# GSM.net
KiCad netlist of a schematic drawn in Altium Designer
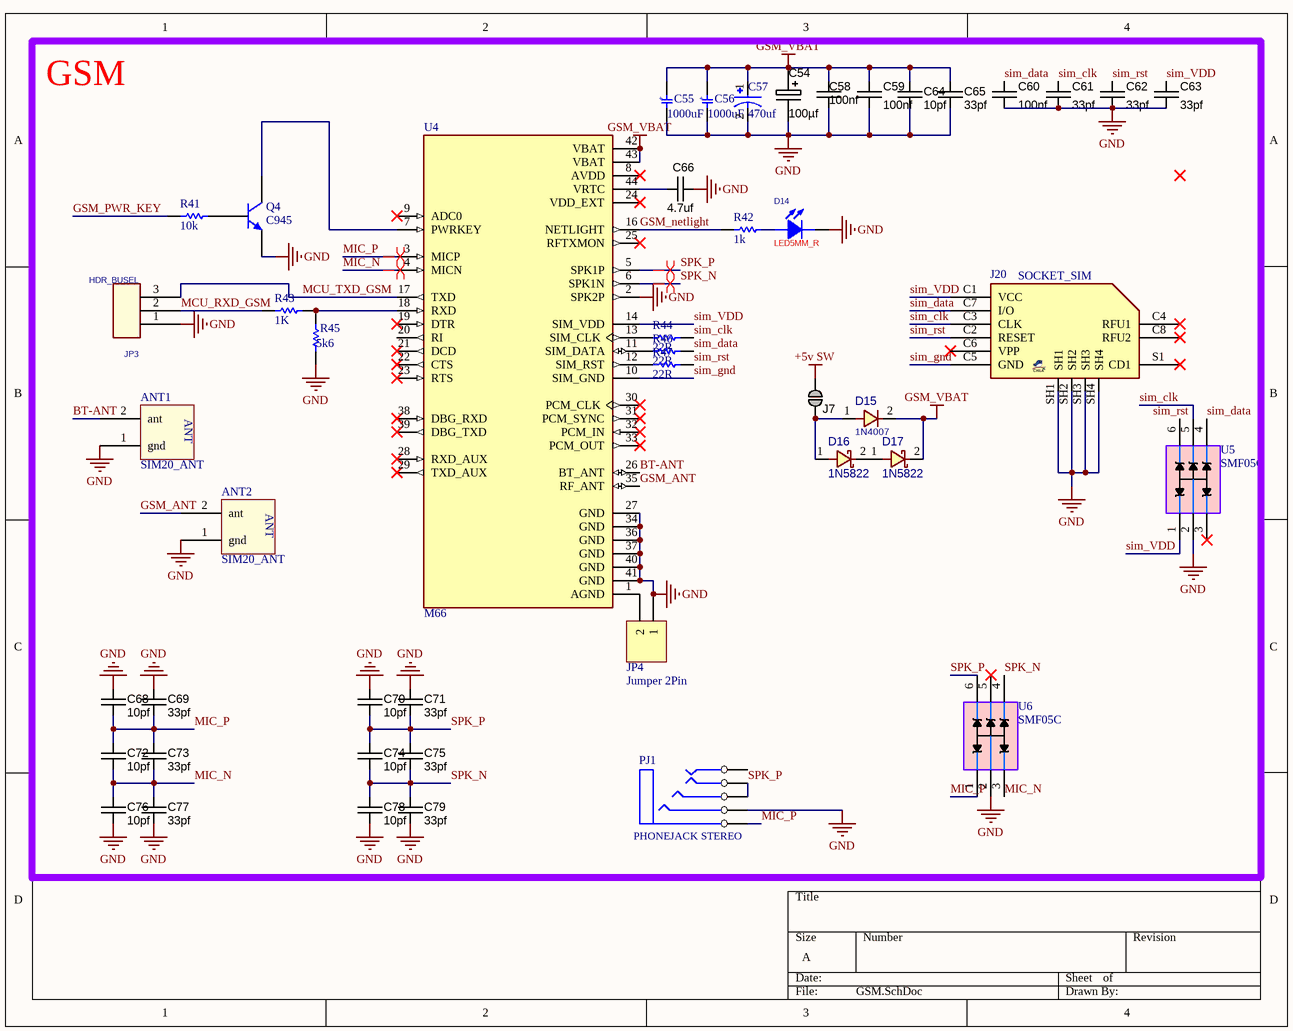
[diagram p0: GSM.SchDoc]

(export (version "E")
  (design (tool "Eeschema 10.0.6"))
  (components
    (comp (ref "ANT1")
      (value "SIM20_ANT")
      (footprint "MY_SIM20_ANT")
      (description "ANT")
      (libsource (lib "altium-import") (part "root_2_SIM20_ANT_"))
    )
    (comp (ref "ANT2")
      (value "SIM20_ANT")
      (footprint "MY_SIM20_ANT")
      (description "ANT")
      (libsource (lib "altium-import") (part "root_2_SIM20_ANT_"))
    )
    (comp (ref "C54")
      (value "100µf")
      (footprint "CAPMP3528X210N")
      (description "Capacitor SMD Tantalum 100uF 20% 6.3V 1210")
      (fields (field (name "TOLERANCE") "±20%") (field (name "Comment") "100uf"))
      (libsource (lib "altium-import") (part "root_0_CAPT_100u_1210_6V3_"))
    )
    (comp (ref "C55")
      (value "1000uF")
      (footprint "Elko G")
      (description "Capacitor Electrical SMD")
      (libsource (lib "Capacitor") (part "Capacitor Electrical SMD"))
    )
    (comp (ref "C56")
      (value "1000uF")
      (footprint "Elko G")
      (description "Capacitor Electrical SMD")
      (libsource (lib "Capacitor") (part "Capacitor Electrical SMD"))
    )
    (comp (ref "C57")
      (value "470uf")
      (footprint "CAP_4TPB330ML")
      (fields (field (name "MP") "4TPB330ML") (field (name "MF") "Sanyo Electric"))
      (libsource (lib "4TPB330ML") (part "4TPB330ML"))
    )
    (comp (ref "C58")
      (value "100nf")
      (footprint "CAPC1608X90N")
      (description "Capacitor SMD Cer 100nF 10% 50V X7R 0603")
      (fields (field (name "TOLERANCE") "±10%"))
      (libsource (lib "altium-import") (part "root_2_CAPC_100n_0603_X7R_50V_10%_"))
    )
    (comp (ref "C59")
      (value "100nf")
      (footprint "CAPC1608X90N")
      (description "Capacitor SMD Cer 100nF 10% 50V X7R 0603")
      (fields (field (name "TOLERANCE") "±10%"))
      (libsource (lib "altium-import") (part "root_2_CAPC_100n_0603_X7R_50V_10%_"))
    )
    (comp (ref "C60")
      (value "100nf")
      (footprint "CAPC1608X90N")
      (description "Capacitor SMD Cer 100nF 10% 50V X7R 0603")
      (fields (field (name "TOLERANCE") "±10%"))
      (libsource (lib "altium-import") (part "root_2_CAPC_100n_0603_X7R_50V_10%_"))
    )
    (comp (ref "C61")
      (value "33pf")
      (footprint "CAPC1608X90N")
      (description "Capacitor SMD Cer 100nF 10% 50V X7R 0603")
      (fields (field (name "TOLERANCE") "±10%"))
      (libsource (lib "altium-import") (part "root_2_CAPC_100n_0603_X7R_50V_10%_"))
    )
    (comp (ref "C62")
      (value "33pf")
      (footprint "CAPC1608X90N")
      (description "Capacitor SMD Cer 100nF 10% 50V X7R 0603")
      (fields (field (name "TOLERANCE") "±10%"))
      (libsource (lib "altium-import") (part "root_2_CAPC_100n_0603_X7R_50V_10%_"))
    )
    (comp (ref "C63")
      (value "33pf")
      (footprint "CAPC1608X90N")
      (description "Capacitor SMD Cer 100nF 10% 50V X7R 0603")
      (fields (field (name "TOLERANCE") "±10%"))
      (libsource (lib "altium-import") (part "root_2_CAPC_100n_0603_X7R_50V_10%_"))
    )
    (comp (ref "C64")
      (value "10pf")
      (footprint "CAPC1608X90N")
      (description "Capacitor SMD Cer 100nF 10% 50V X7R 0603")
      (fields (field (name "TOLERANCE") "±10%"))
      (libsource (lib "altium-import") (part "root_2_CAPC_100n_0603_X7R_50V_10%_"))
    )
    (comp (ref "C65")
      (value "33pf")
      (footprint "CAPC1608X90N")
      (description "Capacitor SMD Cer 100nF 10% 50V X7R 0603")
      (fields (field (name "TOLERANCE") "±10%"))
      (libsource (lib "altium-import") (part "root_2_CAPC_100n_0603_X7R_50V_10%_"))
    )
    (comp (ref "C66")
      (value "4.7uf")
      (footprint "CAPC1608X90N")
      (description "Capacitor SMD Cer 100nF 10% 50V X7R 0603")
      (fields (field (name "TOLERANCE") "±10%"))
      (libsource (lib "altium-import") (part "root_1_CAPC_100n_0603_X7R_50V_10%_"))
    )
    (comp (ref "C68")
      (value "10pf")
      (footprint "CAPC1608X90N")
      (description "Capacitor SMD Cer 100nF 10% 50V X7R 0603")
      (fields (field (name "TOLERANCE") "±10%"))
      (libsource (lib "altium-import") (part "root_2_CAPC_100n_0603_X7R_50V_10%_"))
    )
    (comp (ref "C69")
      (value "33pf")
      (footprint "CAPC1608X90N")
      (description "Capacitor SMD Cer 100nF 10% 50V X7R 0603")
      (fields (field (name "TOLERANCE") "±10%"))
      (libsource (lib "altium-import") (part "root_2_CAPC_100n_0603_X7R_50V_10%_"))
    )
    (comp (ref "C70")
      (value "10pf")
      (footprint "CAPC1608X90N")
      (description "Capacitor SMD Cer 100nF 10% 50V X7R 0603")
      (fields (field (name "TOLERANCE") "±10%"))
      (libsource (lib "altium-import") (part "root_2_CAPC_100n_0603_X7R_50V_10%_"))
    )
    (comp (ref "C71")
      (value "33pf")
      (footprint "CAPC1608X90N")
      (description "Capacitor SMD Cer 100nF 10% 50V X7R 0603")
      (fields (field (name "TOLERANCE") "±10%"))
      (libsource (lib "altium-import") (part "root_2_CAPC_100n_0603_X7R_50V_10%_"))
    )
    (comp (ref "C72")
      (value "10pf")
      (footprint "CAPC1608X90N")
      (description "Capacitor SMD Cer 100nF 10% 50V X7R 0603")
      (fields (field (name "TOLERANCE") "±10%"))
      (libsource (lib "altium-import") (part "root_2_CAPC_100n_0603_X7R_50V_10%_"))
    )
    (comp (ref "C73")
      (value "33pf")
      (footprint "CAPC1608X90N")
      (description "Capacitor SMD Cer 100nF 10% 50V X7R 0603")
      (fields (field (name "TOLERANCE") "±10%"))
      (libsource (lib "altium-import") (part "root_2_CAPC_100n_0603_X7R_50V_10%_"))
    )
    (comp (ref "C74")
      (value "10pf")
      (footprint "CAPC1608X90N")
      (description "Capacitor SMD Cer 100nF 10% 50V X7R 0603")
      (fields (field (name "TOLERANCE") "±10%"))
      (libsource (lib "altium-import") (part "root_2_CAPC_100n_0603_X7R_50V_10%_"))
    )
    (comp (ref "C75")
      (value "33pf")
      (footprint "CAPC1608X90N")
      (description "Capacitor SMD Cer 100nF 10% 50V X7R 0603")
      (fields (field (name "TOLERANCE") "±10%"))
      (libsource (lib "altium-import") (part "root_2_CAPC_100n_0603_X7R_50V_10%_"))
    )
    (comp (ref "C76")
      (value "10pf")
      (footprint "CAPC1608X90N")
      (description "Capacitor SMD Cer 100nF 10% 50V X7R 0603")
      (fields (field (name "TOLERANCE") "±10%"))
      (libsource (lib "altium-import") (part "root_2_CAPC_100n_0603_X7R_50V_10%_"))
    )
    (comp (ref "C77")
      (value "33pf")
      (footprint "CAPC1608X90N")
      (description "Capacitor SMD Cer 100nF 10% 50V X7R 0603")
      (fields (field (name "TOLERANCE") "±10%"))
      (libsource (lib "altium-import") (part "root_2_CAPC_100n_0603_X7R_50V_10%_"))
    )
    (comp (ref "C78")
      (value "10pf")
      (footprint "CAPC1608X90N")
      (description "Capacitor SMD Cer 100nF 10% 50V X7R 0603")
      (fields (field (name "TOLERANCE") "±10%"))
      (libsource (lib "altium-import") (part "root_2_CAPC_100n_0603_X7R_50V_10%_"))
    )
    (comp (ref "C79")
      (value "33pf")
      (footprint "CAPC1608X90N")
      (description "Capacitor SMD Cer 100nF 10% 50V X7R 0603")
      (fields (field (name "TOLERANCE") "±10%"))
      (libsource (lib "altium-import") (part "root_2_CAPC_100n_0603_X7R_50V_10%_"))
    )
    (comp (ref "D14")
      (value "LED5MM_R")
      (footprint "LED5MM_RED")
      (description "LED LIGHTING")
      (fields (field (name "DESIGNER") "Abbas Basereh"))
      (libsource (lib "altium-import") (part "root_0_LED5MM_"))
    )
    (comp (ref "D15")
      (value "1N4007")
      (footprint "D_SMA")
      (description "DIODE, GENERAL PURPOSE, 1000V/1A")
      (fields (field (name "MANF") "Kingtronics") (field (name "MANF_P#") "M7"))
      (libsource (lib "altium-import") (part "root_0_DIODE_SMD_1N4007_"))
    )
    (comp (ref "D16")
      (value "1N5822")
      (footprint "D_SMA")
      (description "DIODE, SCHOTTKY, 40V, 3A")
      (fields (field (name "MANF") "DIODES"))
      (libsource (lib "altium-import") (part "root_0_DIODE_SMD_SCHOTTKY_1N5822_"))
    )
    (comp (ref "D17")
      (value "1N5822")
      (footprint "D_SMA")
      (description "DIODE, SCHOTTKY, 40V, 3A")
      (fields (field (name "MANF") "DIODES"))
      (libsource (lib "altium-import") (part "root_0_DIODE_SMD_SCHOTTKY_1N5822_"))
    )
    (comp (ref "J7")
      (value "Jumper")
      (footprint "JUMP1")
      (description "SMD jumper")
      (libsource (lib "Utiliti_Library") (part "JUMP1"))
    )
    (comp (ref "J20")
      (value "SOCKET_SIM")
      (footprint "SIM_MICRO_GCT")
      (description "SOCKET, SIM MICRO, PUSH/PUSH, SIM7100")
      (fields (field (name "MANF") "GCT") (field (name "MANF_P#") "SIM7100"))
      (libsource (lib "socket_card") (part "SIM_MICRO_GCT"))
    )
    (comp (ref "JP3")
      (value "HDR_BUSEL")
      (footprint "HDR_1x3")
      (description "header or jumper box")
      (libsource (lib "2017AbbasBasereh9365731239 -ver1") (part "Header 1x3"))
    )
    (comp (ref "JP4")
      (value "Jumper 2Pin")
      (footprint "Jumper Small - 2.54 - Blue")
      (description "Jumper, 2-Pin")
      (fields (field (name "DESIGNER") "Abbas Basereh"))
      (libsource (lib "altium-import") (part "root_3_Jumper 2Pin_"))
    )
    (comp (ref "PJ1")
      (value "PHONEJACK STEREO")
      (footprint "PHONE-J2-3.5MM")
      (libsource (lib "*") (part "PHONEJACK STEREO SW"))
    )
    (comp (ref "Q4")
      (value "C945")
      (footprint "SOT23_N")
      (description "NPN Silicon Epitaxial Planar Transistor")
      (fields (field (name "PUBLISHER") "Abbas Basereh"))
      (libsource (lib "altium-import") (part "root_0_C945_"))
    )
    (comp (ref "R41")
      (value "10k")
      (footprint "Resistor_SMD_0603 (1608)")
      (description "Resistor 0603")
      (fields (field (name "PUBLISHER") "Seyed Razi Vesali") (field (name "EMAIL") "razi.vesali@gmail.com"))
      (libsource (lib "resistors") (part "Resistor"))
    )
    (comp (ref "R42")
      (value "1k")
      (footprint "Resistor_SMD_0603 (1608)")
      (description "Resistor 0603")
      (fields (field (name "PUBLISHER") "Seyed Razi Vesali") (field (name "EMAIL") "razi.vesali@gmail.com"))
      (libsource (lib "resistors") (part "Resistor"))
    )
    (comp (ref "R43")
      (value "1K")
      (footprint "Resistor_SMD_0603 (1608)")
      (description "Resistor 0603")
      (fields (field (name "PUBLISHER") "Seyed Razi Vesali") (field (name "EMAIL") "razi.vesali@gmail.com"))
      (libsource (lib "resistors") (part "Resistor"))
    )
    (comp (ref "R44")
      (value "22R")
      (footprint "Resistor_SMD_0603 (1608)")
      (description "Resistor 0603")
      (fields (field (name "PUBLISHER") "Seyed Razi Vesali") (field (name "EMAIL") "razi.vesali@gmail.com"))
      (libsource (lib "resistors") (part "Resistor"))
    )
    (comp (ref "R45")
      (value "5k6")
      (footprint "Resistor_SMD_0603 (1608)")
      (description "Resistor 0603")
      (fields (field (name "PUBLISHER") "Seyed Razi Vesali") (field (name "EMAIL") "razi.vesali@gmail.com"))
      (libsource (lib "resistors") (part "Resistor"))
    )
    (comp (ref "R46")
      (value "22R")
      (footprint "Resistor_SMD_0603 (1608)")
      (description "Resistor 0603")
      (fields (field (name "PUBLISHER") "Seyed Razi Vesali") (field (name "EMAIL") "razi.vesali@gmail.com"))
      (libsource (lib "resistors") (part "Resistor"))
    )
    (comp (ref "R47")
      (value "22R")
      (footprint "Resistor_SMD_0603 (1608)")
      (description "Resistor 0603")
      (fields (field (name "PUBLISHER") "Seyed Razi Vesali") (field (name "EMAIL") "razi.vesali@gmail.com"))
      (libsource (lib "resistors") (part "Resistor"))
    )
    (comp (ref "U4")
      (value "M66")
      (footprint "XCVR_M66")
      (fields (field (name "MF") "Quectel"))
      (libsource (lib "altium-import") (part "root_0_M66_"))
    )
    (comp (ref "U5")
      (value "SMF05C")
      (footprint "SC706")
      (description "TVS Diode Array  For ESD and Latch-Up Protection")
      (libsource (lib "altium-import") (part "root_1_TVS Diode_"))
    )
    (comp (ref "U6")
      (value "SMF05C")
      (footprint "SC706")
      (description "TVS Diode Array  For ESD and Latch-Up Protection")
      (libsource (lib "altium-import") (part "root_1_TVS Diode_"))
    )
  )
  (nets
    (net (code "1") (name "+5v SW") (class "Default") (node (ref "J7") (pin "1") (pintype "passive")))
    (net (code "2") (name "/BT-ANT") (class "Default")
      (node (ref "ANT1") (pin "2") (pinfunction "ant_2") (pintype "passive"))
      (node (ref "U4") (pin "26") (pinfunction "BT_ANT_26") (pintype "bidirectional"))
    )
    (net (code "3") (name "/GSM_ANT") (class "Default")
      (node (ref "ANT2") (pin "2") (pinfunction "ant_2") (pintype "passive"))
      (node (ref "U4") (pin "35") (pinfunction "RF_ANT_35") (pintype "bidirectional"))
    )
    (net (code "4") (name "/GSM_PWR_KEY") (class "Default")
      (node (ref "R41") (pin "1") (pinfunction "1_1") (pintype "passive"))
    )
    (net (code "5") (name "/GSM_netlight") (class "Default")
      (node (ref "R42") (pin "1") (pinfunction "1_1") (pintype "passive"))
      (node (ref "U4") (pin "16") (pinfunction "NETLIGHT_16") (pintype "output"))
    )
    (net (code "6") (name "/MCU_RXD_GSM") (class "Default")
      (node (ref "JP3") (pin "2") (pinfunction "2_2") (pintype "passive"))
      (node (ref "R43") (pin "1") (pinfunction "1_1") (pintype "passive"))
    )
    (net (code "7") (name "/MCU_TXD_GSM") (class "Default")
      (node (ref "JP3") (pin "3") (pinfunction "3_3") (pintype "passive"))
      (node (ref "U4") (pin "17") (pinfunction "TXD_17") (pintype "output"))
    )
    (net (code "8") (name "/MIC_N") (class "Default")
      (node (ref "C72") (pin "1") (pintype "passive"))
      (node (ref "C73") (pin "1") (pintype "passive"))
      (node (ref "C76") (pin "2") (pintype "passive"))
      (node (ref "C77") (pin "2") (pintype "passive"))
      (node (ref "U4") (pin "4") (pinfunction "MICN_4") (pintype "input"))
      (node (ref "U6") (pin "3") (pinfunction "L3_3") (pintype "passive"))
    )
    (net (code "9") (name "/MIC_P") (class "Default")
      (node (ref "C68") (pin "1") (pintype "passive"))
      (node (ref "C69") (pin "1") (pintype "passive"))
      (node (ref "C72") (pin "2") (pintype "passive"))
      (node (ref "C73") (pin "2") (pintype "passive"))
      (node (ref "PJ1") (pin "MIC") (pinfunction "6_MIC") (pintype "passive"))
      (node (ref "U4") (pin "3") (pinfunction "MICP_3") (pintype "input"))
      (node (ref "U6") (pin "1") (pinfunction "L1_1") (pintype "passive"))
    )
    (net (code "10") (name "/SPK_N") (class "Default")
      (node (ref "C74") (pin "1") (pintype "passive"))
      (node (ref "C75") (pin "1") (pintype "passive"))
      (node (ref "C78") (pin "2") (pintype "passive"))
      (node (ref "C79") (pin "2") (pintype "passive"))
      (node (ref "U4") (pin "6") (pinfunction "SPK1N_6") (pintype "output"))
      (node (ref "U6") (pin "4") (pinfunction "L4_4") (pintype "passive"))
    )
    (net (code "11") (name "/SPK_P") (class "Default")
      (node (ref "C70") (pin "1") (pintype "passive"))
      (node (ref "C71") (pin "1") (pintype "passive"))
      (node (ref "C74") (pin "2") (pintype "passive"))
      (node (ref "C75") (pin "2") (pintype "passive"))
      (node (ref "PJ1") (pin "EL") (pinfunction "3_EL") (pintype "passive"))
      (node (ref "PJ1") (pin "ER") (pinfunction "4_ER") (pintype "passive"))
      (node (ref "U4") (pin "5") (pinfunction "SPK1P_5") (pintype "output"))
      (node (ref "U6") (pin "6") (pinfunction "L6_6") (pintype "passive"))
    )
    (net (code "12") (name "/sim_VDD") (class "Default")
      (node (ref "C63") (pin "2") (pintype "passive"))
      (node (ref "J20") (pin "C1") (pinfunction "VCC_C1") (pintype "passive"))
      (node (ref "U4") (pin "14") (pinfunction "SIM_VDD_14") (pintype "power_in"))
      (node (ref "U5") (pin "1") (pinfunction "L1_1") (pintype "passive"))
    )
    (net (code "13") (name "/sim_clk") (class "Default")
      (node (ref "C61") (pin "2") (pintype "passive"))
      (node (ref "J20") (pin "C3") (pinfunction "CLK_C3") (pintype "passive"))
      (node (ref "R44") (pin "2") (pinfunction "2_2") (pintype "passive"))
      (node (ref "U5") (pin "5") (pinfunction "L5_5") (pintype "passive"))
    )
    (net (code "14") (name "/sim_data") (class "Default")
      (node (ref "C60") (pin "2") (pintype "passive"))
      (node (ref "J20") (pin "C7") (pinfunction "I/O_C7") (pintype "passive"))
      (node (ref "R46") (pin "2") (pinfunction "2_2") (pintype "passive"))
      (node (ref "U5") (pin "4") (pinfunction "L4_4") (pintype "passive"))
    )
    (net (code "15") (name "/sim_gnd") (class "Default")
      (node (ref "J20") (pin "C5") (pinfunction "GND_C5") (pintype "passive"))
      (node (ref "U4") (pin "10") (pinfunction "SIM_GND_10") (pintype "power_in"))
    )
    (net (code "16") (name "/sim_rst") (class "Default")
      (node (ref "C62") (pin "2") (pintype "passive"))
      (node (ref "J20") (pin "C2") (pinfunction "RESET_C2") (pintype "passive"))
      (node (ref "R47") (pin "2") (pinfunction "2_2") (pintype "passive"))
    )
    (net (code "17") (name "GND") (class "Default")
      (node (ref "ANT1") (pin "1") (pinfunction "gnd_1") (pintype "passive"))
      (node (ref "ANT2") (pin "1") (pinfunction "gnd_1") (pintype "passive"))
      (node (ref "C54") (pin "2") (pintype "passive"))
      (node (ref "C55") (pin "1") (pinfunction "1_1") (pintype "passive"))
      (node (ref "C56") (pin "1") (pinfunction "1_1") (pintype "passive"))
      (node (ref "C57") (pin "2") (pinfunction "2_2") (pintype "passive"))
      (node (ref "C58") (pin "1") (pintype "passive"))
      (node (ref "C59") (pin "1") (pintype "passive"))
      (node (ref "C60") (pin "1") (pintype "passive"))
      (node (ref "C61") (pin "1") (pintype "passive"))
      (node (ref "C62") (pin "1") (pintype "passive"))
      (node (ref "C63") (pin "1") (pintype "passive"))
      (node (ref "C64") (pin "1") (pintype "passive"))
      (node (ref "C65") (pin "1") (pintype "passive"))
      (node (ref "C66") (pin "2") (pintype "passive"))
      (node (ref "C68") (pin "2") (pintype "passive"))
      (node (ref "C69") (pin "2") (pintype "passive"))
      (node (ref "C70") (pin "2") (pintype "passive"))
      (node (ref "C71") (pin "2") (pintype "passive"))
      (node (ref "C76") (pin "1") (pintype "passive"))
      (node (ref "C77") (pin "1") (pintype "passive"))
      (node (ref "C78") (pin "1") (pintype "passive"))
      (node (ref "C79") (pin "1") (pintype "passive"))
      (node (ref "D14") (pin "2") (pinfunction "CATHODE_2") (pintype "passive"))
      (node (ref "J20") (pin "SH1") (pinfunction "SH1_SH1") (pintype "passive"))
      (node (ref "J20") (pin "SH2") (pinfunction "SH2_SH2") (pintype "passive"))
      (node (ref "J20") (pin "SH3") (pinfunction "SH3_SH3") (pintype "passive"))
      (node (ref "J20") (pin "SH4") (pinfunction "SH4_SH4") (pintype "passive"))
      (node (ref "JP3") (pin "1") (pinfunction "1_1") (pintype "passive"))
      (node (ref "JP4") (pin "1") (pinfunction "1_1") (pintype "passive"))
      (node (ref "PJ1") (pin "GND") (pinfunction "5_GND") (pintype "passive"))
      (node (ref "Q4") (pin "2") (pinfunction "E_2") (pintype "passive"))
      (node (ref "R45") (pin "2") (pinfunction "2_2") (pintype "passive"))
      (node (ref "U4") (pin "2") (pinfunction "SPK2P_2") (pintype "output"))
      (node (ref "U4") (pin "27") (pinfunction "GND_27") (pintype "power_in"))
      (node (ref "U4") (pin "34") (pinfunction "GND_34") (pintype "power_in"))
      (node (ref "U4") (pin "36") (pinfunction "GND_36") (pintype "power_in"))
      (node (ref "U4") (pin "37") (pinfunction "GND_37") (pintype "power_in"))
      (node (ref "U4") (pin "40") (pinfunction "GND_40") (pintype "power_in"))
      (node (ref "U4") (pin "41") (pinfunction "GND_41") (pintype "power_in"))
      (node (ref "U5") (pin "2") (pinfunction "Gnd_2") (pintype "passive"))
      (node (ref "U6") (pin "2") (pinfunction "Gnd_2") (pintype "passive"))
    )
    (net (code "18") (name "GSM_VBAT") (class "Default")
      (node (ref "C54") (pin "1") (pintype "passive"))
      (node (ref "C55") (pin "2") (pinfunction "2_2") (pintype "passive"))
      (node (ref "C56") (pin "2") (pinfunction "2_2") (pintype "passive"))
      (node (ref "C57") (pin "1") (pinfunction "1_1") (pintype "passive"))
      (node (ref "C58") (pin "2") (pintype "passive"))
      (node (ref "C59") (pin "2") (pintype "passive"))
      (node (ref "C64") (pin "2") (pintype "passive"))
      (node (ref "C65") (pin "2") (pintype "passive"))
      (node (ref "D15") (pin "2") (pinfunction "2_2") (pintype "passive"))
      (node (ref "D17") (pin "2") (pinfunction "2_2") (pintype "passive"))
      (node (ref "U4") (pin "42") (pinfunction "VBAT_42") (pintype "power_in"))
      (node (ref "U4") (pin "43") (pinfunction "VBAT_43") (pintype "power_in"))
    )
    (net (code "19") (name "Net-(D14-ANODE)") (class "Default")
      (node (ref "D14") (pin "1") (pinfunction "ANODE_1") (pintype "passive"))
      (node (ref "R42") (pin "2") (pinfunction "2_2") (pintype "passive"))
    )
    (net (code "20") (name "Net-(D15-Pad1)") (class "Default")
      (node (ref "D15") (pin "1") (pinfunction "1_1") (pintype "passive"))
      (node (ref "D16") (pin "1") (pinfunction "1_1") (pintype "passive"))
      (node (ref "J7") (pin "2") (pintype "passive"))
    )
    (net (code "21") (name "Net-(D16-Pad2)") (class "Default")
      (node (ref "D16") (pin "2") (pinfunction "2_2") (pintype "passive"))
      (node (ref "D17") (pin "1") (pinfunction "1_1") (pintype "passive"))
    )
    (net (code "22") (name "Net-(Q4-B)") (class "Default")
      (node (ref "Q4") (pin "1") (pinfunction "B_1") (pintype "passive"))
      (node (ref "R41") (pin "2") (pinfunction "2_2") (pintype "passive"))
    )
    (net (code "23") (name "Net-(Q4-C)") (class "Default")
      (node (ref "Q4") (pin "3") (pinfunction "C_3") (pintype "passive"))
      (node (ref "U4") (pin "7") (pinfunction "PWRKEY_7") (pintype "input"))
    )
    (net (code "24") (name "Net-(U4-AGND)") (class "Default")
      (node (ref "JP4") (pin "2") (pinfunction "2_2") (pintype "passive"))
      (node (ref "U4") (pin "1") (pinfunction "AGND_1") (pintype "power_in"))
    )
    (net (code "25") (name "Net-(U4-RXD)") (class "Default")
      (node (ref "R43") (pin "2") (pinfunction "2_2") (pintype "passive"))
      (node (ref "R45") (pin "1") (pinfunction "1_1") (pintype "passive"))
      (node (ref "U4") (pin "18") (pinfunction "RXD_18") (pintype "input"))
    )
    (net (code "26") (name "Net-(U4-SIM_CLK)") (class "Default")
      (node (ref "R44") (pin "1") (pinfunction "1_1") (pintype "passive"))
      (node (ref "U4") (pin "13") (pinfunction "SIM_CLK_13") (pintype "output"))
    )
    (net (code "27") (name "Net-(U4-SIM_DATA)") (class "Default")
      (node (ref "R46") (pin "1") (pinfunction "1_1") (pintype "passive"))
      (node (ref "U4") (pin "11") (pinfunction "SIM_DATA_11") (pintype "bidirectional"))
    )
    (net (code "28") (name "Net-(U4-SIM_RST)") (class "Default")
      (node (ref "R47") (pin "1") (pinfunction "1_1") (pintype "passive"))
      (node (ref "U4") (pin "12") (pinfunction "SIM_RST_12") (pintype "output"))
    )
    (net (code "29") (name "Net-(U4-VRTC)") (class "Default")
      (node (ref "C66") (pin "1") (pintype "passive"))
      (node (ref "U4") (pin "44") (pinfunction "VRTC_44") (pintype "power_in"))
    )
    (net (code "30") (name "unconnected-(J20-CD1-PadS1)") (class "Default")
      (node (ref "J20") (pin "S1") (pinfunction "CD1_S1") (pintype "passive+no_connect"))
    )
    (net (code "31") (name "unconnected-(J20-RFU1-PadC4)") (class "Default")
      (node (ref "J20") (pin "C4") (pinfunction "RFU1_C4") (pintype "passive+no_connect"))
    )
    (net (code "32") (name "unconnected-(J20-RFU2-PadC8)") (class "Default")
      (node (ref "J20") (pin "C8") (pinfunction "RFU2_C8") (pintype "passive+no_connect"))
    )
    (net (code "33") (name "unconnected-(J20-VPP-PadC6)") (class "Default")
      (node (ref "J20") (pin "C6") (pinfunction "VPP_C6") (pintype "passive+no_connect"))
    )
    (net (code "34") (name "unconnected-(PJ1-2-PadPD)") (class "Default")
      (node (ref "PJ1") (pin "PD") (pinfunction "2_PD") (pintype "passive"))
    )
    (net (code "35") (name "unconnected-(U4-ADC0-Pad9)") (class "Default")
      (node (ref "U4") (pin "9") (pinfunction "ADC0_9") (pintype "input+no_connect"))
    )
    (net (code "36") (name "unconnected-(U4-AVDD-Pad8)") (class "Default")
      (node (ref "U4") (pin "8") (pinfunction "AVDD_8") (pintype "power_in+no_connect"))
    )
    (net (code "37") (name "unconnected-(U4-CTS-Pad22)") (class "Default")
      (node (ref "U4") (pin "22") (pinfunction "CTS_22") (pintype "output+no_connect"))
    )
    (net (code "38") (name "unconnected-(U4-DBG_RXD-Pad38)") (class "Default")
      (node (ref "U4") (pin "38") (pinfunction "DBG_RXD_38") (pintype "input+no_connect"))
    )
    (net (code "39") (name "unconnected-(U4-DBG_TXD-Pad39)") (class "Default")
      (node (ref "U4") (pin "39") (pinfunction "DBG_TXD_39") (pintype "output+no_connect"))
    )
    (net (code "40") (name "unconnected-(U4-DCD-Pad21)") (class "Default")
      (node (ref "U4") (pin "21") (pinfunction "DCD_21") (pintype "output+no_connect"))
    )
    (net (code "41") (name "unconnected-(U4-DTR-Pad19)") (class "Default")
      (node (ref "U4") (pin "19") (pinfunction "DTR_19") (pintype "input+no_connect"))
    )
    (net (code "42") (name "unconnected-(U4-PCM_CLK-Pad30)") (class "Default")
      (node (ref "U4") (pin "30") (pinfunction "PCM_CLK_30") (pintype "output+no_connect"))
    )
    (net (code "43") (name "unconnected-(U4-PCM_IN-Pad32)") (class "Default")
      (node (ref "U4") (pin "32") (pinfunction "PCM_IN_32") (pintype "input+no_connect"))
    )
    (net (code "44") (name "unconnected-(U4-PCM_OUT-Pad33)") (class "Default")
      (node (ref "U4") (pin "33") (pinfunction "PCM_OUT_33") (pintype "output+no_connect"))
    )
    (net (code "45") (name "unconnected-(U4-PCM_SYNC-Pad31)") (class "Default")
      (node (ref "U4") (pin "31") (pinfunction "PCM_SYNC_31") (pintype "output+no_connect"))
    )
    (net (code "46") (name "unconnected-(U4-RFTXMON-Pad25)") (class "Default")
      (node (ref "U4") (pin "25") (pinfunction "RFTXMON_25") (pintype "output+no_connect"))
    )
    (net (code "47") (name "unconnected-(U4-RI-Pad20)") (class "Default")
      (node (ref "U4") (pin "20") (pinfunction "RI_20") (pintype "output"))
    )
    (net (code "48") (name "unconnected-(U4-RTS-Pad23)") (class "Default")
      (node (ref "U4") (pin "23") (pinfunction "RTS_23") (pintype "input+no_connect"))
    )
    (net (code "49") (name "unconnected-(U4-RXD_AUX-Pad28)") (class "Default")
      (node (ref "U4") (pin "28") (pinfunction "RXD_AUX_28") (pintype "input+no_connect"))
    )
    (net (code "50") (name "unconnected-(U4-TXD_AUX-Pad29)") (class "Default")
      (node (ref "U4") (pin "29") (pinfunction "TXD_AUX_29") (pintype "output+no_connect"))
    )
    (net (code "51") (name "unconnected-(U4-VDD_EXT-Pad24)") (class "Default")
      (node (ref "U4") (pin "24") (pinfunction "VDD_EXT_24") (pintype "power_in+no_connect"))
    )
    (net (code "52") (name "unconnected-(U5-L3-Pad3)") (class "Default")
      (node (ref "U5") (pin "3") (pinfunction "L3_3") (pintype "passive+no_connect"))
    )
    (net (code "53") (name "unconnected-(U5-L6-Pad6)") (class "Default")
      (node (ref "U5") (pin "6") (pinfunction "L6_6") (pintype "passive"))
    )
    (net (code "54") (name "unconnected-(U6-L5-Pad5)") (class "Default")
      (node (ref "U6") (pin "5") (pinfunction "L5_5") (pintype "passive+no_connect"))
    )
  )
)
